# hula_poppy.net
KiCad netlist of a schematic drawn in EAGLE
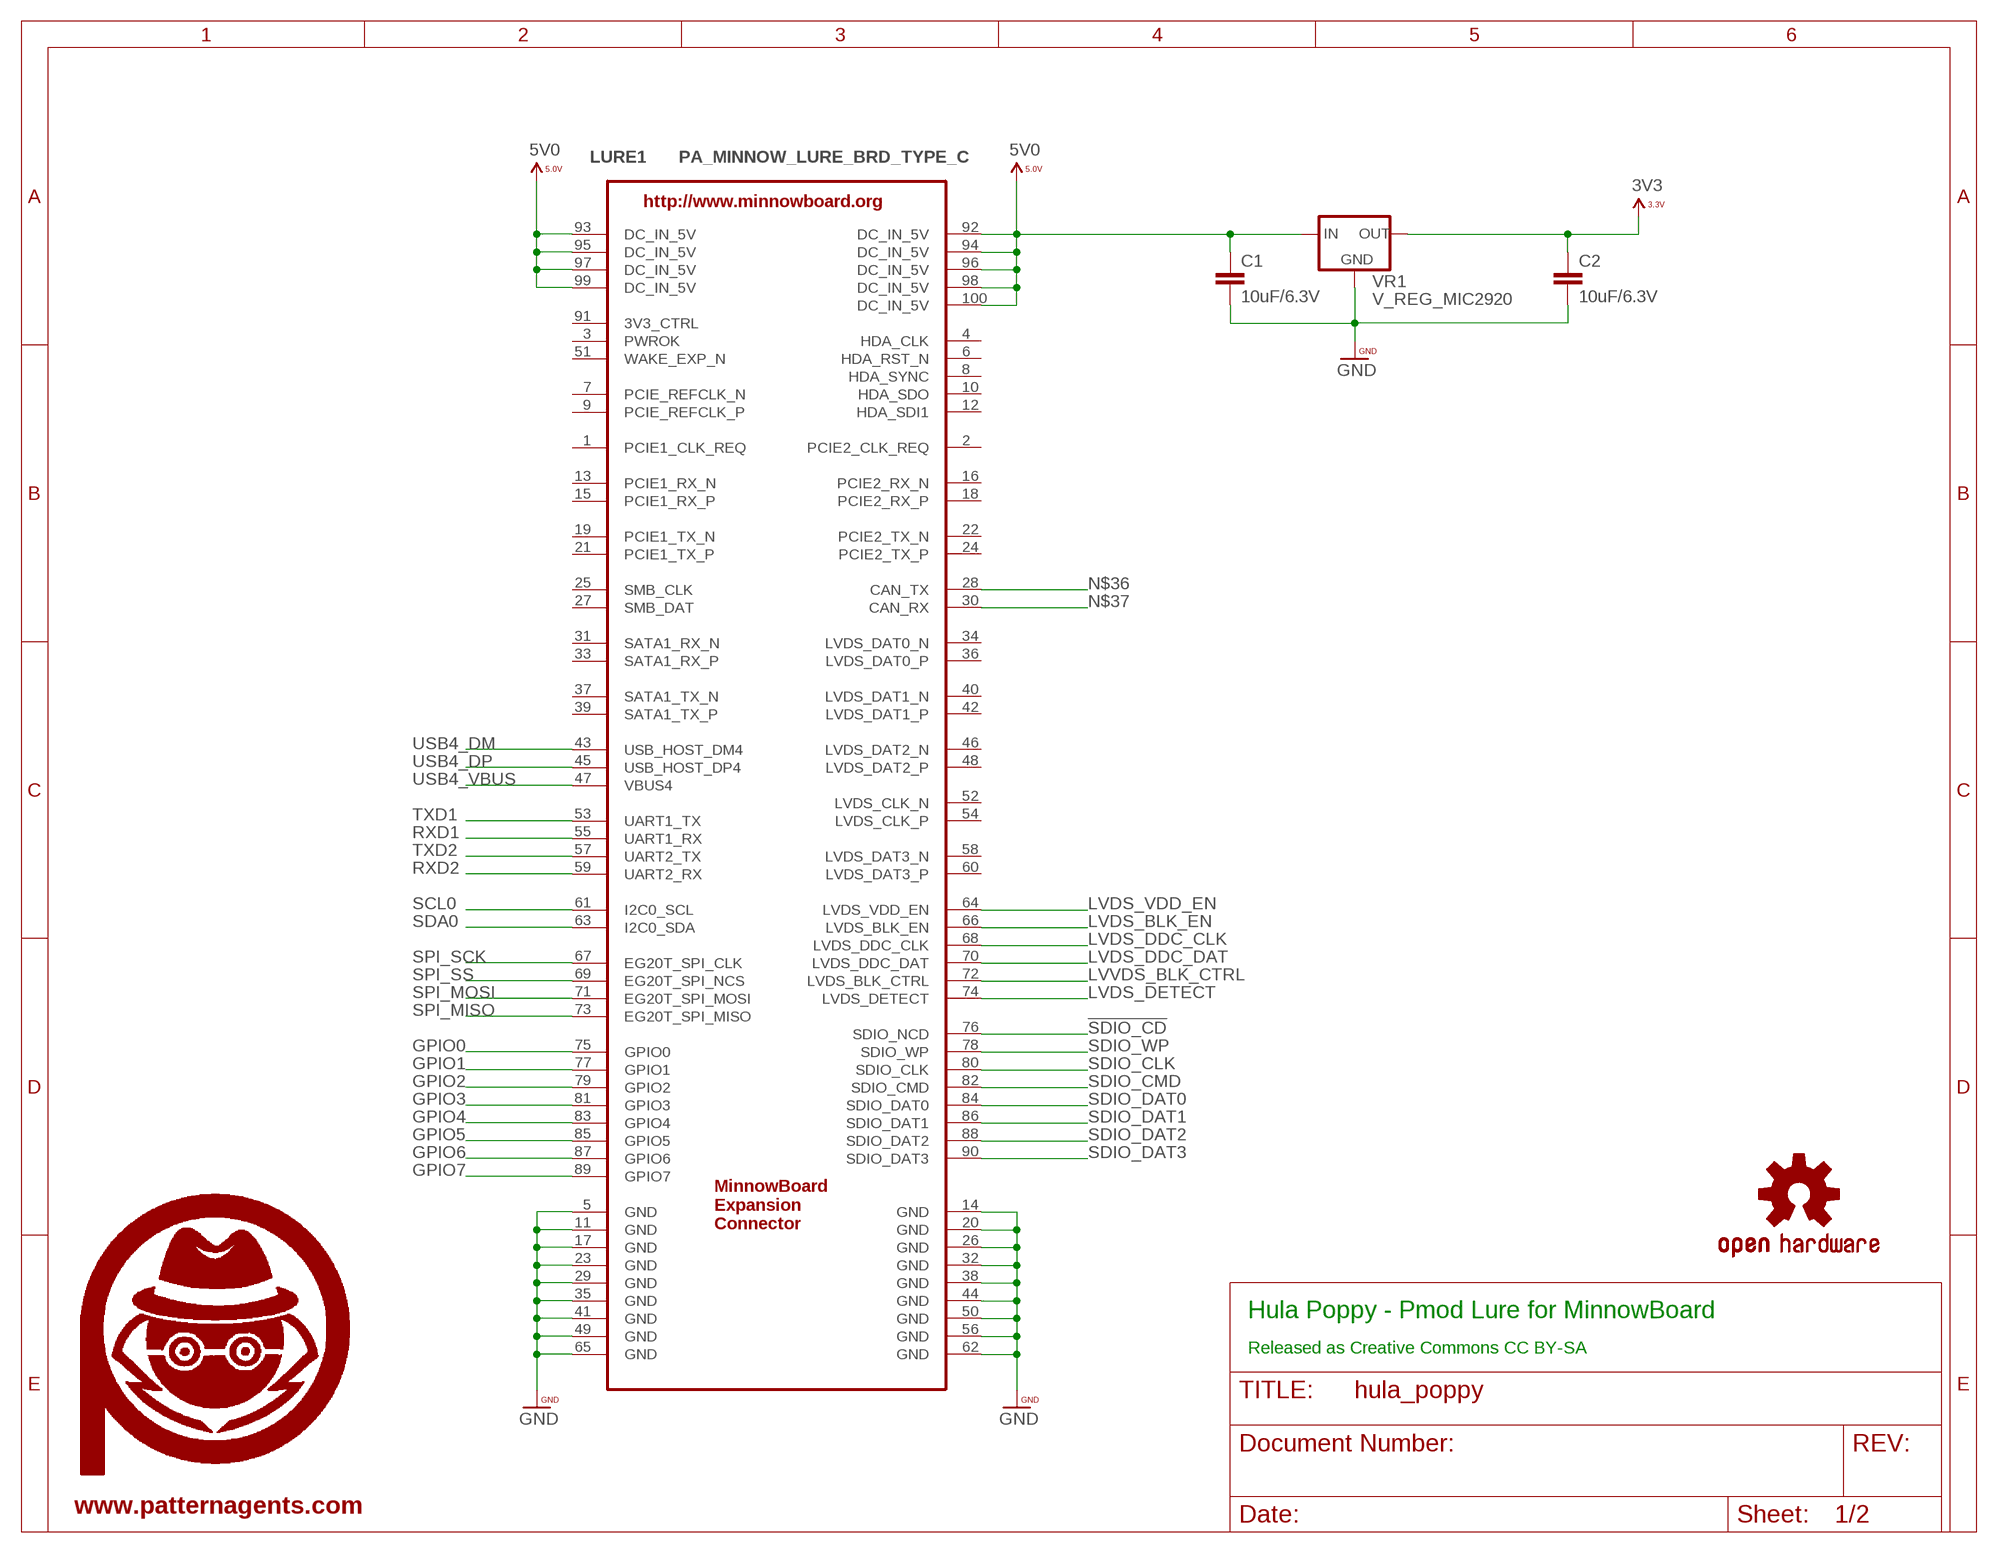
[diagram p0: schematic, sheet 1]
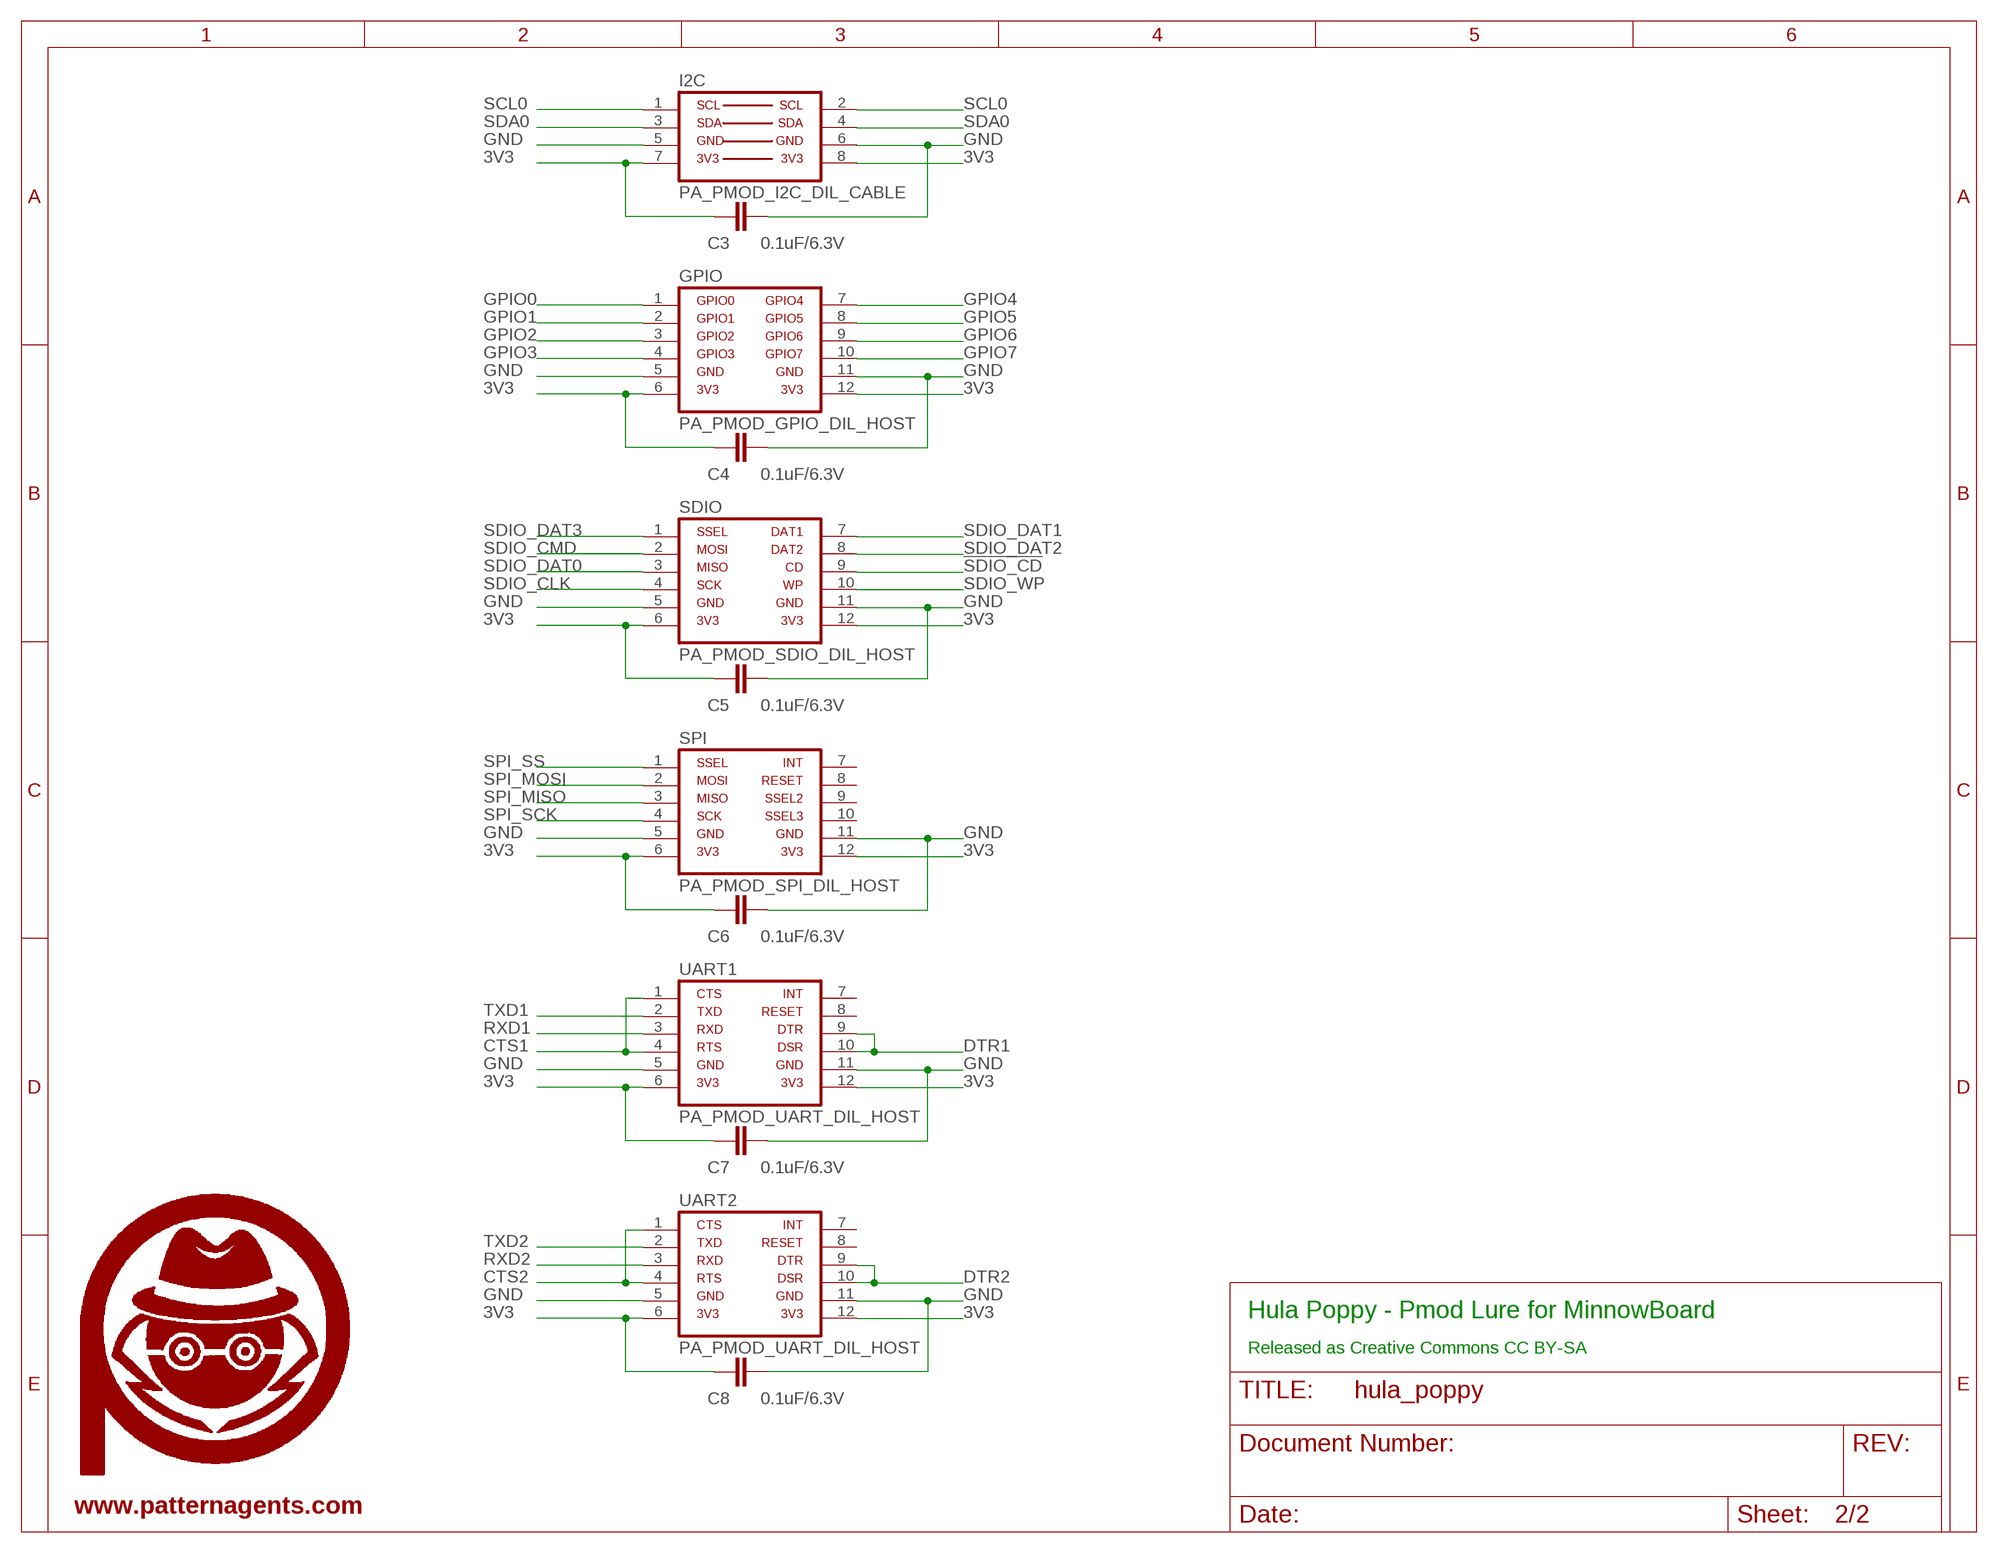
[diagram p1: schematic, sheet 2]

(export (version "E")
  (design (tool "Eeschema 10.0.6"))
  (components
    (comp (ref "C1")
      (value "10uF/6.3V")
      (footprint "eagle-import:0603-CAP")
      (libsource (lib "eagle-import") (part "CAP0603-CAP"))
    )
    (comp (ref "C2")
      (value "10uF/6.3V")
      (footprint "eagle-import:0603-CAP")
      (libsource (lib "eagle-import") (part "CAP0603-CAP"))
    )
    (comp (ref "LURE1")
      (value "PA_MINNOW_LURE_BRD_TYPE_C")
      (footprint "eagle-import:PA_LURE_TYPE_C")
      (libsource (lib "eagle-import") (part "PA_MINNOW_LURE_BRD_TYPE_C"))
    )
    (comp (ref "U$6")
      (value "PA_LOGO_SYMMED")
      (footprint "eagle-import:PA_LOGO_AGENT_MED_SYM")
      (libsource (lib "eagle-import") (part "PA_LOGO_SYMMED"))
    )
    (comp (ref "U$8")
      (value "OSHW_LOGO_SYMWTXT")
      (footprint "eagle-import:OSHW_LOGO_TEXT_SYM")
      (libsource (lib "eagle-import") (part "OSHW_LOGO_SYMWTXT"))
    )
    (comp (ref "VR1")
      (value "V_REG_MIC2920")
      (footprint "eagle-import:SOT223")
      (libsource (lib "eagle-import") (part "V_REG_MIC2920"))
    )
    (comp (ref "C3")
      (value "0.1uF/6.3V")
      (footprint "eagle-import:0603-CAP")
      (libsource (lib "eagle-import") (part "CAP0603-CAP"))
    )
    (comp (ref "C4")
      (value "0.1uF/6.3V")
      (footprint "eagle-import:0603-CAP")
      (libsource (lib "eagle-import") (part "CAP0603-CAP"))
    )
    (comp (ref "C5")
      (value "0.1uF/6.3V")
      (footprint "eagle-import:0603-CAP")
      (libsource (lib "eagle-import") (part "CAP0603-CAP"))
    )
    (comp (ref "C6")
      (value "0.1uF/6.3V")
      (footprint "eagle-import:0603-CAP")
      (libsource (lib "eagle-import") (part "CAP0603-CAP"))
    )
    (comp (ref "C7")
      (value "0.1uF/6.3V")
      (footprint "eagle-import:0603-CAP")
      (libsource (lib "eagle-import") (part "CAP0603-CAP"))
    )
    (comp (ref "C8")
      (value "0.1uF/6.3V")
      (footprint "eagle-import:0603-CAP")
      (libsource (lib "eagle-import") (part "CAP0603-CAP"))
    )
    (comp (ref "GPIO")
      (value "PA_PMOD_GPIO_DIL_HOST")
      (footprint "eagle-import:PA_PMOD_DIL_FEMALE")
      (libsource (lib "eagle-import") (part "PA_PMOD_GPIO_DIL_HOST"))
    )
    (comp (ref "I2C")
      (value "PA_PMOD_I2C_DIL_CABLE")
      (footprint "eagle-import:PA_PMOD_I2C_CABLE")
      (libsource (lib "eagle-import") (part "PA_PMOD_I2C_DIL_CABLE"))
    )
    (comp (ref "SDIO")
      (value "PA_PMOD_SDIO_DIL_HOST")
      (footprint "eagle-import:PA_PMOD_DIL_FEMALE")
      (libsource (lib "eagle-import") (part "PA_PMOD_SDIO_DIL_HOST"))
    )
    (comp (ref "SPI")
      (value "PA_PMOD_SPI_DIL_HOST")
      (footprint "eagle-import:PA_PMOD_DIL_FEMALE")
      (libsource (lib "eagle-import") (part "PA_PMOD_SPI_DIL_HOST"))
    )
    (comp (ref "U$10")
      (value "PA_LOGO_SYMMED")
      (footprint "eagle-import:PA_LOGO_AGENT_MED_SYM")
      (libsource (lib "eagle-import") (part "PA_LOGO_SYMMED"))
    )
    (comp (ref "UART1")
      (value "PA_PMOD_UART_DIL_HOST")
      (footprint "eagle-import:PA_PMOD_DIL_FEMALE")
      (libsource (lib "eagle-import") (part "PA_PMOD_UART_DIL_HOST"))
    )
    (comp (ref "UART2")
      (value "PA_PMOD_UART_DIL_HOST")
      (footprint "eagle-import:PA_PMOD_DIL_FEMALE")
      (libsource (lib "eagle-import") (part "PA_PMOD_UART_DIL_HOST"))
    )
  )
  (nets
    (net (code "1") (name "3V3") (class "Default")
      (node (ref "C2") (pin "1") (pinfunction "1_1") (pintype "passive"))
      (node (ref "C3") (pin "2") (pinfunction "2_2") (pintype "passive"))
      (node (ref "C4") (pin "2") (pinfunction "2_2") (pintype "passive"))
      (node (ref "C5") (pin "2") (pinfunction "2_2") (pintype "passive"))
      (node (ref "C6") (pin "2") (pinfunction "2_2") (pintype "passive"))
      (node (ref "C7") (pin "2") (pinfunction "2_2") (pintype "passive"))
      (node (ref "C8") (pin "2") (pinfunction "2_2") (pintype "passive"))
      (node (ref "GPIO") (pin "12") (pinfunction "12_12") (pintype "passive"))
      (node (ref "GPIO") (pin "6") (pinfunction "6_6") (pintype "passive"))
      (node (ref "I2C") (pin "7") (pinfunction "7_7") (pintype "passive"))
      (node (ref "I2C") (pin "8") (pinfunction "8_8") (pintype "passive"))
      (node (ref "SDIO") (pin "12") (pinfunction "12_12") (pintype "passive"))
      (node (ref "SDIO") (pin "6") (pinfunction "6_6") (pintype "passive"))
      (node (ref "SPI") (pin "12") (pinfunction "12_12") (pintype "passive"))
      (node (ref "SPI") (pin "6") (pinfunction "6_6") (pintype "passive"))
      (node (ref "UART1") (pin "12") (pinfunction "12_12") (pintype "passive"))
      (node (ref "UART1") (pin "6") (pinfunction "6_6") (pintype "passive"))
      (node (ref "UART2") (pin "12") (pinfunction "12_12") (pintype "passive"))
      (node (ref "UART2") (pin "6") (pinfunction "6_6") (pintype "passive"))
      (node (ref "VR1") (pin "3") (pinfunction "OUT_3") (pintype "output"))
    )
    (net (code "2") (name "3V3_CTRL") (class "Default")
      (node (ref "LURE1") (pin "91") (pinfunction "3V3_CTRL_91") (pintype "power_in"))
    )
    (net (code "3") (name "5V0") (class "Default")
      (node (ref "C1") (pin "1") (pinfunction "1_1") (pintype "passive"))
      (node (ref "LURE1") (pin "100") (pinfunction "DC_IN_5V_100") (pintype "power_in"))
      (node (ref "LURE1") (pin "92") (pinfunction "DC_IN_5V_92") (pintype "power_in"))
      (node (ref "LURE1") (pin "93") (pinfunction "DC_IN_5V_93") (pintype "power_in"))
      (node (ref "LURE1") (pin "94") (pinfunction "DC_IN_5V_94") (pintype "power_in"))
      (node (ref "LURE1") (pin "95") (pinfunction "DC_IN_5V_95") (pintype "power_in"))
      (node (ref "LURE1") (pin "96") (pinfunction "DC_IN_5V_96") (pintype "power_in"))
      (node (ref "LURE1") (pin "97") (pinfunction "DC_IN_5V_97") (pintype "power_in"))
      (node (ref "LURE1") (pin "98") (pinfunction "DC_IN_5V_98") (pintype "power_in"))
      (node (ref "LURE1") (pin "99") (pinfunction "DC_IN_5V_99") (pintype "power_in"))
      (node (ref "VR1") (pin "1") (pinfunction "IN_1") (pintype "input"))
    )
    (net (code "4") (name "CTS1") (class "Default")
      (node (ref "UART1") (pin "1") (pinfunction "1_1") (pintype "passive"))
      (node (ref "UART1") (pin "4") (pinfunction "4_4") (pintype "passive"))
    )
    (net (code "5") (name "CTS2") (class "Default")
      (node (ref "UART2") (pin "1") (pinfunction "1_1") (pintype "passive"))
      (node (ref "UART2") (pin "4") (pinfunction "4_4") (pintype "passive"))
    )
    (net (code "6") (name "DTR1") (class "Default")
      (node (ref "UART1") (pin "10") (pinfunction "10_10") (pintype "passive"))
      (node (ref "UART1") (pin "9") (pinfunction "9_9") (pintype "passive"))
    )
    (net (code "7") (name "DTR2") (class "Default")
      (node (ref "UART2") (pin "10") (pinfunction "10_10") (pintype "passive"))
      (node (ref "UART2") (pin "9") (pinfunction "9_9") (pintype "passive"))
    )
    (net (code "8") (name "GND") (class "Default")
      (node (ref "C1") (pin "2") (pinfunction "2_2") (pintype "passive"))
      (node (ref "C2") (pin "2") (pinfunction "2_2") (pintype "passive"))
      (node (ref "C3") (pin "1") (pinfunction "1_1") (pintype "passive"))
      (node (ref "C4") (pin "1") (pinfunction "1_1") (pintype "passive"))
      (node (ref "C5") (pin "1") (pinfunction "1_1") (pintype "passive"))
      (node (ref "C6") (pin "1") (pinfunction "1_1") (pintype "passive"))
      (node (ref "C7") (pin "1") (pinfunction "1_1") (pintype "passive"))
      (node (ref "C8") (pin "1") (pinfunction "1_1") (pintype "passive"))
      (node (ref "GPIO") (pin "11") (pinfunction "11_11") (pintype "passive"))
      (node (ref "GPIO") (pin "5") (pinfunction "5_5") (pintype "passive"))
      (node (ref "I2C") (pin "5") (pinfunction "5_5") (pintype "passive"))
      (node (ref "I2C") (pin "6") (pinfunction "6_6") (pintype "passive"))
      (node (ref "LURE1") (pin "11") (pinfunction "GND_11") (pintype "power_in"))
      (node (ref "LURE1") (pin "14") (pinfunction "GND_14") (pintype "power_in"))
      (node (ref "LURE1") (pin "17") (pinfunction "GND_17") (pintype "power_in"))
      (node (ref "LURE1") (pin "20") (pinfunction "GND_20") (pintype "power_in"))
      (node (ref "LURE1") (pin "23") (pinfunction "GND_23") (pintype "power_in"))
      (node (ref "LURE1") (pin "26") (pinfunction "GND_26") (pintype "power_in"))
      (node (ref "LURE1") (pin "29") (pinfunction "GND_29") (pintype "power_in"))
      (node (ref "LURE1") (pin "32") (pinfunction "GND_32") (pintype "power_in"))
      (node (ref "LURE1") (pin "35") (pinfunction "GND_35") (pintype "power_in"))
      (node (ref "LURE1") (pin "38") (pinfunction "GND_38") (pintype "power_in"))
      (node (ref "LURE1") (pin "41") (pinfunction "GND_41") (pintype "power_in"))
      (node (ref "LURE1") (pin "44") (pinfunction "GND_44") (pintype "power_in"))
      (node (ref "LURE1") (pin "49") (pinfunction "GND_49") (pintype "power_in"))
      (node (ref "LURE1") (pin "5") (pinfunction "GND_5") (pintype "power_in"))
      (node (ref "LURE1") (pin "50") (pinfunction "GND_50") (pintype "power_in"))
      (node (ref "LURE1") (pin "56") (pinfunction "GND_56") (pintype "power_in"))
      (node (ref "LURE1") (pin "62") (pinfunction "GND_62") (pintype "power_in"))
      (node (ref "LURE1") (pin "65") (pinfunction "GND_65") (pintype "power_in"))
      (node (ref "SDIO") (pin "11") (pinfunction "11_11") (pintype "passive"))
      (node (ref "SDIO") (pin "5") (pinfunction "5_5") (pintype "passive"))
      (node (ref "SPI") (pin "11") (pinfunction "11_11") (pintype "passive"))
      (node (ref "SPI") (pin "5") (pinfunction "5_5") (pintype "passive"))
      (node (ref "UART1") (pin "11") (pinfunction "11_11") (pintype "passive"))
      (node (ref "UART1") (pin "5") (pinfunction "5_5") (pintype "passive"))
      (node (ref "UART2") (pin "11") (pinfunction "11_11") (pintype "passive"))
      (node (ref "UART2") (pin "5") (pinfunction "5_5") (pintype "passive"))
      (node (ref "VR1") (pin "2") (pinfunction "GND_2") (pintype "input"))
    )
    (net (code "9") (name "GPIO0") (class "Default")
      (node (ref "GPIO") (pin "1") (pinfunction "1_1") (pintype "passive"))
      (node (ref "LURE1") (pin "75") (pinfunction "GPIO0_75") (pintype "bidirectional"))
    )
    (net (code "10") (name "GPIO1") (class "Default")
      (node (ref "GPIO") (pin "2") (pinfunction "2_2") (pintype "passive"))
      (node (ref "LURE1") (pin "77") (pinfunction "GPIO1_77") (pintype "bidirectional"))
    )
    (net (code "11") (name "GPIO2") (class "Default")
      (node (ref "GPIO") (pin "3") (pinfunction "3_3") (pintype "passive"))
      (node (ref "LURE1") (pin "79") (pinfunction "GPIO2_79") (pintype "bidirectional"))
    )
    (net (code "12") (name "GPIO3") (class "Default")
      (node (ref "GPIO") (pin "4") (pinfunction "4_4") (pintype "passive"))
      (node (ref "LURE1") (pin "81") (pinfunction "GPIO3_81") (pintype "bidirectional"))
    )
    (net (code "13") (name "GPIO4") (class "Default")
      (node (ref "GPIO") (pin "7") (pinfunction "7_7") (pintype "passive"))
      (node (ref "LURE1") (pin "83") (pinfunction "GPIO4_83") (pintype "bidirectional"))
    )
    (net (code "14") (name "GPIO5") (class "Default")
      (node (ref "GPIO") (pin "8") (pinfunction "8_8") (pintype "passive"))
      (node (ref "LURE1") (pin "85") (pinfunction "GPIO5_85") (pintype "bidirectional"))
    )
    (net (code "15") (name "GPIO6") (class "Default")
      (node (ref "GPIO") (pin "9") (pinfunction "9_9") (pintype "passive"))
      (node (ref "LURE1") (pin "87") (pinfunction "GPIO6_87") (pintype "bidirectional"))
    )
    (net (code "16") (name "GPIO7") (class "Default")
      (node (ref "GPIO") (pin "10") (pinfunction "10_10") (pintype "passive"))
      (node (ref "LURE1") (pin "89") (pinfunction "GPIO7_89") (pintype "bidirectional"))
    )
    (net (code "17") (name "LVDS_BLK_EN") (class "Default")
      (node (ref "LURE1") (pin "66") (pinfunction "LVDS_BLK_EN_66") (pintype "bidirectional"))
    )
    (net (code "18") (name "LVDS_DDC_CLK") (class "Default")
      (node (ref "LURE1") (pin "68") (pinfunction "LVDS_DDC_CLK_68") (pintype "bidirectional"))
    )
    (net (code "19") (name "LVDS_DDC_DAT") (class "Default")
      (node (ref "LURE1") (pin "70") (pinfunction "LVDS_DDC_DAT_70") (pintype "bidirectional"))
    )
    (net (code "20") (name "LVDS_DETECT") (class "Default")
      (node (ref "LURE1") (pin "74") (pinfunction "LVDS_DETECT_74") (pintype "bidirectional"))
    )
    (net (code "21") (name "LVDS_VDD_EN") (class "Default")
      (node (ref "LURE1") (pin "64") (pinfunction "LVDS_VDD_EN_64") (pintype "bidirectional"))
    )
    (net (code "22") (name "LVVDS_BLK_CTRL") (class "Default")
      (node (ref "LURE1") (pin "72") (pinfunction "LVDS_BLK_CTRL_72") (pintype "bidirectional"))
    )
    (net (code "23") (name "N$36") (class "Default")
      (node (ref "LURE1") (pin "28") (pinfunction "CAN_TX_28") (pintype "bidirectional"))
    )
    (net (code "24") (name "N$37") (class "Default")
      (node (ref "LURE1") (pin "30") (pinfunction "CAN_RX_30") (pintype "bidirectional"))
    )
    (net (code "25") (name "RXD1") (class "Default")
      (node (ref "LURE1") (pin "55") (pinfunction "UART1_RX_55") (pintype "bidirectional"))
      (node (ref "UART1") (pin "3") (pinfunction "3_3") (pintype "passive"))
    )
    (net (code "26") (name "RXD2") (class "Default")
      (node (ref "LURE1") (pin "59") (pinfunction "UART2_RX_59") (pintype "bidirectional"))
      (node (ref "UART2") (pin "3") (pinfunction "3_3") (pintype "passive"))
    )
    (net (code "27") (name "SCL0") (class "Default")
      (node (ref "I2C") (pin "1") (pinfunction "1_1") (pintype "passive"))
      (node (ref "I2C") (pin "2") (pinfunction "2_2") (pintype "passive"))
      (node (ref "LURE1") (pin "61") (pinfunction "I2C0_SCL_61") (pintype "bidirectional"))
    )
    (net (code "28") (name "SDA0") (class "Default")
      (node (ref "I2C") (pin "3") (pinfunction "3_3") (pintype "passive"))
      (node (ref "I2C") (pin "4") (pinfunction "4_4") (pintype "passive"))
      (node (ref "LURE1") (pin "63") (pinfunction "I2C0_SDA_63") (pintype "bidirectional"))
    )
    (net (code "29") (name "SDIO_CLK") (class "Default")
      (node (ref "LURE1") (pin "80") (pinfunction "SDIO_CLK_80") (pintype "bidirectional"))
      (node (ref "SDIO") (pin "4") (pinfunction "4_4") (pintype "passive"))
    )
    (net (code "30") (name "SDIO_CMD") (class "Default")
      (node (ref "LURE1") (pin "82") (pinfunction "SDIO_CMD_82") (pintype "bidirectional"))
      (node (ref "SDIO") (pin "2") (pinfunction "2_2") (pintype "passive"))
    )
    (net (code "31") (name "SDIO_DAT0") (class "Default")
      (node (ref "LURE1") (pin "84") (pinfunction "SDIO_DAT0_84") (pintype "bidirectional"))
      (node (ref "SDIO") (pin "3") (pinfunction "3_3") (pintype "passive"))
    )
    (net (code "32") (name "SDIO_DAT1") (class "Default")
      (node (ref "LURE1") (pin "86") (pinfunction "SDIO_DAT1_86") (pintype "bidirectional"))
      (node (ref "SDIO") (pin "7") (pinfunction "7_7") (pintype "passive"))
    )
    (net (code "33") (name "SDIO_DAT2") (class "Default")
      (node (ref "LURE1") (pin "88") (pinfunction "SDIO_DAT2_88") (pintype "bidirectional"))
      (node (ref "SDIO") (pin "8") (pinfunction "8_8") (pintype "passive"))
    )
    (net (code "34") (name "SDIO_DAT3") (class "Default")
      (node (ref "LURE1") (pin "90") (pinfunction "SDIO_DAT3_90") (pintype "bidirectional"))
      (node (ref "SDIO") (pin "1") (pinfunction "1_1") (pintype "passive"))
    )
    (net (code "35") (name "SDIO_WP") (class "Default")
      (node (ref "LURE1") (pin "78") (pinfunction "SDIO_WP_78") (pintype "bidirectional"))
      (node (ref "SDIO") (pin "10") (pinfunction "10_10") (pintype "passive"))
    )
    (net (code "36") (name "SPI_MISO") (class "Default")
      (node (ref "LURE1") (pin "73") (pinfunction "EG20T_SPI_MISO_73") (pintype "bidirectional"))
      (node (ref "SPI") (pin "3") (pinfunction "3_3") (pintype "passive"))
    )
    (net (code "37") (name "SPI_MOSI") (class "Default")
      (node (ref "LURE1") (pin "71") (pinfunction "EG20T_SPI_MOSI_71") (pintype "bidirectional"))
      (node (ref "SPI") (pin "2") (pinfunction "2_2") (pintype "passive"))
    )
    (net (code "38") (name "SPI_SCK") (class "Default")
      (node (ref "LURE1") (pin "67") (pinfunction "EG20T_SPI_CLK_67") (pintype "bidirectional"))
      (node (ref "SPI") (pin "4") (pinfunction "4_4") (pintype "passive"))
    )
    (net (code "39") (name "SPI_SS") (class "Default")
      (node (ref "LURE1") (pin "69") (pinfunction "EG20T_SPI_NCS_69") (pintype "bidirectional"))
      (node (ref "SPI") (pin "1") (pinfunction "1_1") (pintype "passive"))
    )
    (net (code "40") (name "TXD1") (class "Default")
      (node (ref "LURE1") (pin "53") (pinfunction "UART1_TX_53") (pintype "bidirectional"))
      (node (ref "UART1") (pin "2") (pinfunction "2_2") (pintype "passive"))
    )
    (net (code "41") (name "TXD2") (class "Default")
      (node (ref "LURE1") (pin "57") (pinfunction "UART2_TX_57") (pintype "bidirectional"))
      (node (ref "UART2") (pin "2") (pinfunction "2_2") (pintype "passive"))
    )
    (net (code "42") (name "USB4_DM") (class "Default")
      (node (ref "LURE1") (pin "43") (pinfunction "USB_HOST_DM4_43") (pintype "bidirectional"))
    )
    (net (code "43") (name "USB4_DP") (class "Default")
      (node (ref "LURE1") (pin "45") (pinfunction "USB_HOST_DP4_45") (pintype "bidirectional"))
    )
    (net (code "44") (name "USB4_VBUS") (class "Default")
      (node (ref "LURE1") (pin "47") (pinfunction "VBUS4_47") (pintype "power_in"))
    )
    (net (code "45") (name "unconnected-(LURE1-HDA_CLK-Pad4)") (class "Default")
      (node (ref "LURE1") (pin "4") (pinfunction "HDA_CLK_4") (pintype "bidirectional"))
    )
    (net (code "46") (name "unconnected-(LURE1-HDA_RST_N-Pad6)") (class "Default")
      (node (ref "LURE1") (pin "6") (pinfunction "HDA_RST_N_6") (pintype "bidirectional"))
    )
    (net (code "47") (name "unconnected-(LURE1-HDA_SDI1-Pad12)") (class "Default")
      (node (ref "LURE1") (pin "12") (pinfunction "HDA_SDI1_12") (pintype "bidirectional"))
    )
    (net (code "48") (name "unconnected-(LURE1-HDA_SDO-Pad10)") (class "Default")
      (node (ref "LURE1") (pin "10") (pinfunction "HDA_SDO_10") (pintype "bidirectional"))
    )
    (net (code "49") (name "unconnected-(LURE1-HDA_SYNC-Pad8)") (class "Default")
      (node (ref "LURE1") (pin "8") (pinfunction "HDA_SYNC_8") (pintype "bidirectional"))
    )
    (net (code "50") (name "unconnected-(LURE1-LVDS_CLK_N-Pad52)") (class "Default")
      (node (ref "LURE1") (pin "52") (pinfunction "LVDS_CLK_N_52") (pintype "bidirectional"))
    )
    (net (code "51") (name "unconnected-(LURE1-LVDS_CLK_P-Pad54)") (class "Default")
      (node (ref "LURE1") (pin "54") (pinfunction "LVDS_CLK_P_54") (pintype "bidirectional"))
    )
    (net (code "52") (name "unconnected-(LURE1-LVDS_DAT0_N-Pad34)") (class "Default")
      (node (ref "LURE1") (pin "34") (pinfunction "LVDS_DAT0_N_34") (pintype "bidirectional"))
    )
    (net (code "53") (name "unconnected-(LURE1-LVDS_DAT0_P-Pad36)") (class "Default")
      (node (ref "LURE1") (pin "36") (pinfunction "LVDS_DAT0_P_36") (pintype "bidirectional"))
    )
    (net (code "54") (name "unconnected-(LURE1-LVDS_DAT1_N-Pad40)") (class "Default")
      (node (ref "LURE1") (pin "40") (pinfunction "LVDS_DAT1_N_40") (pintype "bidirectional"))
    )
    (net (code "55") (name "unconnected-(LURE1-LVDS_DAT1_P-Pad42)") (class "Default")
      (node (ref "LURE1") (pin "42") (pinfunction "LVDS_DAT1_P_42") (pintype "bidirectional"))
    )
    (net (code "56") (name "unconnected-(LURE1-LVDS_DAT2_N-Pad46)") (class "Default")
      (node (ref "LURE1") (pin "46") (pinfunction "LVDS_DAT2_N_46") (pintype "bidirectional"))
    )
    (net (code "57") (name "unconnected-(LURE1-LVDS_DAT2_P-Pad48)") (class "Default")
      (node (ref "LURE1") (pin "48") (pinfunction "LVDS_DAT2_P_48") (pintype "bidirectional"))
    )
    (net (code "58") (name "unconnected-(LURE1-LVDS_DAT3_N-Pad58)") (class "Default")
      (node (ref "LURE1") (pin "58") (pinfunction "LVDS_DAT3_N_58") (pintype "bidirectional"))
    )
    (net (code "59") (name "unconnected-(LURE1-LVDS_DAT3_P-Pad60)") (class "Default")
      (node (ref "LURE1") (pin "60") (pinfunction "LVDS_DAT3_P_60") (pintype "bidirectional"))
    )
    (net (code "60") (name "unconnected-(LURE1-PCIE1_CLK_REQ-Pad1)") (class "Default")
      (node (ref "LURE1") (pin "1") (pinfunction "PCIE1_CLK_REQ_1") (pintype "bidirectional"))
    )
    (net (code "61") (name "unconnected-(LURE1-PCIE1_RX_N-Pad13)") (class "Default")
      (node (ref "LURE1") (pin "13") (pinfunction "PCIE1_RX_N_13") (pintype "bidirectional"))
    )
    (net (code "62") (name "unconnected-(LURE1-PCIE1_RX_P-Pad15)") (class "Default")
      (node (ref "LURE1") (pin "15") (pinfunction "PCIE1_RX_P_15") (pintype "bidirectional"))
    )
    (net (code "63") (name "unconnected-(LURE1-PCIE1_TX_N-Pad19)") (class "Default")
      (node (ref "LURE1") (pin "19") (pinfunction "PCIE1_TX_N_19") (pintype "bidirectional"))
    )
    (net (code "64") (name "unconnected-(LURE1-PCIE1_TX_P-Pad21)") (class "Default")
      (node (ref "LURE1") (pin "21") (pinfunction "PCIE1_TX_P_21") (pintype "bidirectional"))
    )
    (net (code "65") (name "unconnected-(LURE1-PCIE2_CLK_REQ-Pad2)") (class "Default")
      (node (ref "LURE1") (pin "2") (pinfunction "PCIE2_CLK_REQ_2") (pintype "bidirectional"))
    )
    (net (code "66") (name "unconnected-(LURE1-PCIE2_RX_N-Pad16)") (class "Default")
      (node (ref "LURE1") (pin "16") (pinfunction "PCIE2_RX_N_16") (pintype "bidirectional"))
    )
    (net (code "67") (name "unconnected-(LURE1-PCIE2_RX_P-Pad18)") (class "Default")
      (node (ref "LURE1") (pin "18") (pinfunction "PCIE2_RX_P_18") (pintype "bidirectional"))
    )
    (net (code "68") (name "unconnected-(LURE1-PCIE2_TX_N-Pad22)") (class "Default")
      (node (ref "LURE1") (pin "22") (pinfunction "PCIE2_TX_N_22") (pintype "bidirectional"))
    )
    (net (code "69") (name "unconnected-(LURE1-PCIE2_TX_P-Pad24)") (class "Default")
      (node (ref "LURE1") (pin "24") (pinfunction "PCIE2_TX_P_24") (pintype "bidirectional"))
    )
    (net (code "70") (name "unconnected-(LURE1-PCIE_REFCLK_N-Pad7)") (class "Default")
      (node (ref "LURE1") (pin "7") (pinfunction "PCIE_REFCLK_N_7") (pintype "bidirectional"))
    )
    (net (code "71") (name "unconnected-(LURE1-PCIE_REFCLK_P-Pad9)") (class "Default")
      (node (ref "LURE1") (pin "9") (pinfunction "PCIE_REFCLK_P_9") (pintype "bidirectional"))
    )
    (net (code "72") (name "unconnected-(LURE1-PWROK-Pad3)") (class "Default")
      (node (ref "LURE1") (pin "3") (pinfunction "PWROK_3") (pintype "bidirectional"))
    )
    (net (code "73") (name "unconnected-(LURE1-SATA1_RX_N-Pad31)") (class "Default")
      (node (ref "LURE1") (pin "31") (pinfunction "SATA1_RX_N_31") (pintype "bidirectional"))
    )
    (net (code "74") (name "unconnected-(LURE1-SATA1_RX_P-Pad33)") (class "Default")
      (node (ref "LURE1") (pin "33") (pinfunction "SATA1_RX_P_33") (pintype "bidirectional"))
    )
    (net (code "75") (name "unconnected-(LURE1-SATA1_TX_N-Pad37)") (class "Default")
      (node (ref "LURE1") (pin "37") (pinfunction "SATA1_TX_N_37") (pintype "bidirectional"))
    )
    (net (code "76") (name "unconnected-(LURE1-SATA1_TX_P-Pad39)") (class "Default")
      (node (ref "LURE1") (pin "39") (pinfunction "SATA1_TX_P_39") (pintype "bidirectional"))
    )
    (net (code "77") (name "unconnected-(LURE1-SMB_CLK-Pad25)") (class "Default")
      (node (ref "LURE1") (pin "25") (pinfunction "SMB_CLK_25") (pintype "bidirectional"))
    )
    (net (code "78") (name "unconnected-(LURE1-SMB_DAT-Pad27)") (class "Default")
      (node (ref "LURE1") (pin "27") (pinfunction "SMB_DAT_27") (pintype "bidirectional"))
    )
    (net (code "79") (name "unconnected-(LURE1-WAKE_EXP_N-Pad51)") (class "Default")
      (node (ref "LURE1") (pin "51") (pinfunction "WAKE_EXP_N_51") (pintype "bidirectional"))
    )
    (net (code "80") (name "unconnected-(SPI-Pad7)") (class "Default")
      (node (ref "SPI") (pin "7") (pinfunction "7_7") (pintype "passive"))
    )
    (net (code "81") (name "unconnected-(SPI-Pad8)") (class "Default")
      (node (ref "SPI") (pin "8") (pinfunction "8_8") (pintype "passive"))
    )
    (net (code "82") (name "unconnected-(SPI-Pad9)") (class "Default")
      (node (ref "SPI") (pin "9") (pinfunction "9_9") (pintype "passive"))
    )
    (net (code "83") (name "unconnected-(SPI-Pad10)") (class "Default")
      (node (ref "SPI") (pin "10") (pinfunction "10_10") (pintype "passive"))
    )
    (net (code "84") (name "unconnected-(UART1-Pad7)") (class "Default")
      (node (ref "UART1") (pin "7") (pinfunction "7_7") (pintype "passive"))
    )
    (net (code "85") (name "unconnected-(UART1-Pad8)") (class "Default")
      (node (ref "UART1") (pin "8") (pinfunction "8_8") (pintype "passive"))
    )
    (net (code "86") (name "unconnected-(UART2-Pad7)") (class "Default")
      (node (ref "UART2") (pin "7") (pinfunction "7_7") (pintype "passive"))
    )
    (net (code "87") (name "unconnected-(UART2-Pad8)") (class "Default")
      (node (ref "UART2") (pin "8") (pinfunction "8_8") (pintype "passive"))
    )
    (net (code "88") (name "~{SDIO_CD}") (class "Default")
      (node (ref "LURE1") (pin "76") (pinfunction "SDIO_NCD_76") (pintype "bidirectional"))
      (node (ref "SDIO") (pin "9") (pinfunction "9_9") (pintype "passive"))
    )
  )
)
